# 05-TCXO_Crystal.net
KiCad netlist of a schematic drawn in Altium Designer
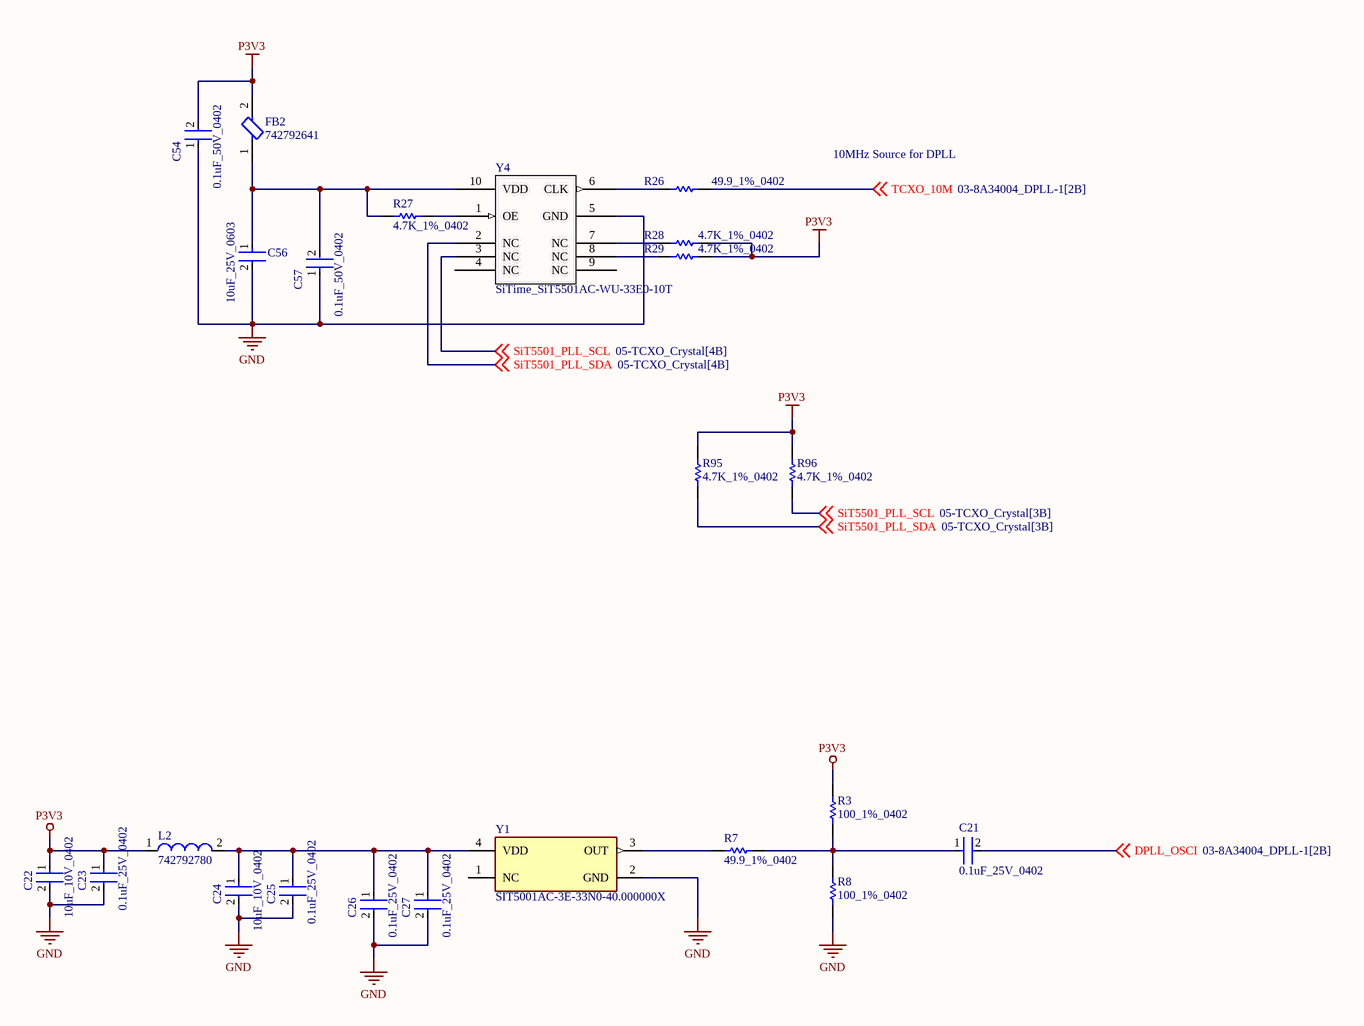
[diagram p0: 05-TCXO_Crystal.SchDoc]

(export (version "E")
  (design (tool "Eeschema 10.0.6"))
  (components
    (comp (ref "C21")
      (value "0.1uF_25V_0402")
      (footprint "FP-0402-L_1_0_1-W_0_5_0_1-IPC_C")
      (description "General Purpose Ceramic Capacitor, 0402, 100nF, 10%, X7R, 15%, 25V")
      (fields (field (name "VOLTAGE") "25V") (field (name "TOLERANCE") "10%"))
      (libsource (lib "Altium Content Vault") (part "b4654b650e69147ec39a6b967a45e02"))
    )
    (comp (ref "C22")
      (value "10uF_10V_0402")
      (footprint "FP-CL05A106MP5NUNC-MFG")
      (description "CAP CER 10UF 10V X5R 0402")
      (fields
        (field (name "OCTOPART") "https://octopart.com/cl05a106mp5nunc-samsung-22457395")
        (field (name "TOLERANCE") "20%")
      )
      (libsource (lib "Altium Content Vault") (part "b4654b650e69147ec39a6b967a45e02"))
    )
    (comp (ref "C23")
      (value "0.1uF_25V_0402")
      (footprint "FP-0402-L_1_0_1-W_0_5_0_1-IPC_C")
      (description "General Purpose Ceramic Capacitor, 0402, 100nF, 10%, X7R, 15%, 25V")
      (fields (field (name "VOLTAGE") "25V") (field (name "TOLERANCE") "10%"))
      (libsource (lib "Altium Content Vault") (part "b4654b650e69147ec39a6b967a45e02"))
    )
    (comp (ref "C24")
      (value "10uF_10V_0402")
      (footprint "FP-CL05A106MP5NUNC-MFG")
      (description "CAP CER 10UF 10V X5R 0402")
      (fields
        (field (name "OCTOPART") "https://octopart.com/cl05a106mp5nunc-samsung-22457395")
        (field (name "TOLERANCE") "20%")
      )
      (libsource (lib "Altium Content Vault") (part "b4654b650e69147ec39a6b967a45e02"))
    )
    (comp (ref "C25")
      (value "0.1uF_25V_0402")
      (footprint "FP-0402-L_1_0_1-W_0_5_0_1-IPC_C")
      (description "General Purpose Ceramic Capacitor, 0402, 100nF, 10%, X7R, 15%, 25V")
      (fields (field (name "VOLTAGE") "25V") (field (name "TOLERANCE") "10%"))
      (libsource (lib "Altium Content Vault") (part "b4654b650e69147ec39a6b967a45e02"))
    )
    (comp (ref "C26")
      (value "0.1uF_25V_0402")
      (footprint "FP-0402-L_1_0_1-W_0_5_0_1-IPC_C")
      (description "General Purpose Ceramic Capacitor, 0402, 100nF, 10%, X7R, 15%, 25V")
      (fields (field (name "VOLTAGE") "25V") (field (name "TOLERANCE") "10%"))
      (libsource (lib "Altium Content Vault") (part "b4654b650e69147ec39a6b967a45e02"))
    )
    (comp (ref "C27")
      (value "0.1uF_25V_0402")
      (footprint "FP-0402-L_1_0_1-W_0_5_0_1-IPC_C")
      (description "General Purpose Ceramic Capacitor, 0402, 100nF, 10%, X7R, 15%, 25V")
      (fields (field (name "VOLTAGE") "25V") (field (name "TOLERANCE") "10%"))
      (libsource (lib "Altium Content Vault") (part "b4654b650e69147ec39a6b967a45e02"))
    )
    (comp (ref "C54")
      (value "0.1uF_50V_0402")
      (footprint "FP-C1005-050-0_05-IPC_C")
      (description "Multilayer Ceramic Capacitors 100nF ±10% 50V X7R SMD 0402")
      (fields (field (name "VOLTAGE") "50V") (field (name "TOLERANCE") "10%"))
      (libsource (lib "Altium Content Vault") (part "b4654b650e69147ec39a6b967a45e02"))
    )
    (comp (ref "C56")
      (value "10uF_25V_0603")
      (footprint "FP-CL10-IPC_C")
      (description "Cap Ceramic 10uF 25V X5R ±20% Pad SMD 0603 +85°C T/R")
      (fields (field (name "TOLERANCE") "20%"))
      (libsource (lib "Altium Content Vault") (part "b4654b650e69147ec39a6b967a45e02"))
    )
    (comp (ref "C57")
      (value "0.1uF_50V_0402")
      (footprint "FP-C1005-050-0_05-IPC_C")
      (description "Multilayer Ceramic Capacitors 100nF ±10% 50V X7R SMD 0402")
      (fields (field (name "VOLTAGE") "50V") (field (name "TOLERANCE") "10%"))
      (libsource (lib "Altium Content Vault") (part "b4654b650e69147ec39a6b967a45e02"))
    )
    (comp (ref "FB2")
      (value "742792641")
      (footprint "FP-742792641-MFG")
      (description "FERRITE BEAD 300 OHM 0603 1LN")
      (fields (field (name "TOLERANCE") "25%"))
      (libsource (lib "Altium Content Vault") (part "5f30dd21d616792df468990f7003faa"))
    )
    (comp (ref "L2")
      (value "742792780")
      (footprint "SMD-0402")
      (description "SMD EMI Suppression Ferrite Bead WE-CBF, Z = 220 Ohm")
      (libsource (lib "Altium Content Vault") (part "PAS-IND-INDUCTOR-2"))
    )
    (comp (ref "R3")
      (value "100_1%_0402")
      (footprint "RESC1005X40X25ML05T10")
      (fields (field (name "PART NUMBER") "ERJ-U02F1000X") (field (name "MANUFACTURER") "Panasonic"))
      (libsource (lib "Altium Content Vault") (part "RES"))
    )
    (comp (ref "R7")
      (value "49.9_1%_0402")
      (footprint "RESC1005X40X25NL10T10")
      (fields (field (name "PART NUMBER") "RK73H1ETTP49R9F") (field (name "MANUFACTURER") "KOA Speer"))
      (libsource (lib "Altium Content Vault") (part "RES"))
    )
    (comp (ref "R8")
      (value "100_1%_0402")
      (footprint "RESC1005X40X25ML05T10")
      (fields (field (name "PART NUMBER") "ERJ-U02F1000X") (field (name "MANUFACTURER") "Panasonic"))
      (libsource (lib "Altium Content Vault") (part "RES"))
    )
    (comp (ref "R26")
      (value "49.9_1%_0402")
      (footprint "RESC1005X40X25NL10T10")
      (fields (field (name "PART NUMBER") "RK73H1ETTP49R9F") (field (name "MANUFACTURER") "KOA Speer"))
      (libsource (lib "Altium Content Vault") (part "RES"))
    )
    (comp (ref "R27")
      (value "4.7K_1%_0402")
      (footprint "RESC1005X40X25NL10T10")
      (fields (field (name "MANUFACTURER") "Bourns") (field (name "PART NUMBER") "CR0402-FX-4701GLF"))
      (libsource (lib "Altium Content Vault") (part "RES"))
    )
    (comp (ref "R28")
      (value "4.7K_1%_0402")
      (footprint "RESC1005X40X25NL10T10")
      (fields (field (name "MANUFACTURER") "Bourns") (field (name "PART NUMBER") "CR0402-FX-4701GLF"))
      (libsource (lib "Altium Content Vault") (part "RES"))
    )
    (comp (ref "R29")
      (value "4.7K_1%_0402")
      (footprint "RESC1005X40X25NL10T10")
      (fields (field (name "MANUFACTURER") "Bourns") (field (name "PART NUMBER") "CR0402-FX-4701GLF"))
      (libsource (lib "Altium Content Vault") (part "RES"))
    )
    (comp (ref "R95")
      (value "4.7K_1%_0402")
      (footprint "RESC1005X40X25NL10T10")
      (fields (field (name "MANUFACTURER") "Bourns") (field (name "PART NUMBER") "CR0402-FX-4701GLF"))
      (libsource (lib "Altium Content Vault") (part "RES"))
    )
    (comp (ref "R96")
      (value "4.7K_1%_0402")
      (footprint "RESC1005X40X25NL10T10")
      (fields (field (name "MANUFACTURER") "Bourns") (field (name "PART NUMBER") "CR0402-FX-4701GLF"))
      (libsource (lib "Altium Content Vault") (part "RES"))
    )
    (comp (ref "Y1")
      (value "SIT5001AC-3E-33N0-40.000000X")
      (footprint "FP-SiT5001-3-MFG")
      (description "MEMS OSC TCXO 40.0000MHZ LVCMOS")
      (libsource (lib "Altium Content Vault") (part "f2b4964c30f19ad016f2c5313c7e3e3"))
    )
    (comp (ref "Y4")
      (value "SiTime_SiT5501AC-WU-33E0-10T")
      (footprint "SITIME_SPL-086-CQFN-010-C07050_REV_DRAFT")
      (description "OSC, MEMS, STRATUM 3E, 10.000MHZ, 10PPB STAB, LVCMOS, 3.3V, O/P EN, 7.0X5.0X2.2MM, CQFN-10")
      (fields
        (field (name "MANUFACTURER PART NUMBER") "SiT5501AI-WU033JH-10.000000")
        (field (name "MANUFACTURER") "SiTime")
      )
      (libsource (lib "OCXO_DaughterCard") (part "CMP-OSC-00029-2"))
    )
  )
  (nets
    (net (code "1") (name "DPLL_OSCI") (class "Default")
      (node (ref "C21") (pin "2") (pinfunction "2_2") (pintype "passive"))
    )
    (net (code "2") (name "GND") (class "Default")
      (node (ref "C22") (pin "2") (pinfunction "2_2") (pintype "passive"))
      (node (ref "C23") (pin "2") (pinfunction "2_2") (pintype "passive"))
      (node (ref "C24") (pin "2") (pinfunction "2_2") (pintype "passive"))
      (node (ref "C25") (pin "2") (pinfunction "2_2") (pintype "passive"))
      (node (ref "C26") (pin "2") (pinfunction "2_2") (pintype "passive"))
      (node (ref "C27") (pin "2") (pinfunction "2_2") (pintype "passive"))
      (node (ref "C54") (pin "1") (pinfunction "1_1") (pintype "passive"))
      (node (ref "C56") (pin "2") (pinfunction "2_2") (pintype "passive"))
      (node (ref "C57") (pin "1") (pinfunction "1_1") (pintype "passive"))
      (node (ref "R8") (pin "1") (pinfunction "1_1") (pintype "passive"))
      (node (ref "Y1") (pin "2") (pinfunction "GND_2") (pintype "power_in"))
      (node (ref "Y4") (pin "5") (pinfunction "GND_5") (pintype "power_in"))
    )
    (net (code "3") (name "Net-(C21-Pad1)") (class "Default")
      (node (ref "C21") (pin "1") (pinfunction "1_1") (pintype "passive"))
      (node (ref "R3") (pin "1") (pinfunction "1_1") (pintype "passive"))
      (node (ref "R7") (pin "2") (pinfunction "2_2") (pintype "passive"))
      (node (ref "R8") (pin "2") (pinfunction "2_2") (pintype "passive"))
    )
    (net (code "4") (name "Net-(R28-Pad1)") (class "Default")
      (node (ref "R28") (pin "1") (pinfunction "1_1") (pintype "passive"))
      (node (ref "Y4") (pin "7") (pinfunction "NC_7") (pintype "passive"))
    )
    (net (code "5") (name "Net-(R29-Pad1)") (class "Default")
      (node (ref "R29") (pin "1") (pinfunction "1_1") (pintype "passive"))
      (node (ref "Y4") (pin "8") (pinfunction "NC_8") (pintype "passive"))
    )
    (net (code "6") (name "Net-(Y1-OUT)") (class "Default")
      (node (ref "R7") (pin "1") (pinfunction "1_1") (pintype "passive"))
      (node (ref "Y1") (pin "3") (pinfunction "OUT_3") (pintype "output"))
    )
    (net (code "7") (name "Net-(Y1-VDD)") (class "Default")
      (node (ref "C24") (pin "1") (pinfunction "1_1") (pintype "passive"))
      (node (ref "C25") (pin "1") (pinfunction "1_1") (pintype "passive"))
      (node (ref "C26") (pin "1") (pinfunction "1_1") (pintype "passive"))
      (node (ref "C27") (pin "1") (pinfunction "1_1") (pintype "passive"))
      (node (ref "L2") (pin "2") (pinfunction "2_2") (pintype "passive"))
      (node (ref "Y1") (pin "4") (pinfunction "VDD_4") (pintype "power_in"))
    )
    (net (code "8") (name "Net-(Y4-CLK)") (class "Default")
      (node (ref "R26") (pin "2") (pinfunction "2_2") (pintype "passive"))
      (node (ref "Y4") (pin "6") (pinfunction "CLK_6") (pintype "output"))
    )
    (net (code "9") (name "Net-(Y4-OE)") (class "Default")
      (node (ref "R27") (pin "2") (pinfunction "2_2") (pintype "passive"))
      (node (ref "Y4") (pin "1") (pinfunction "OE_1") (pintype "input"))
    )
    (net (code "10") (name "Net-(Y4-VDD)") (class "Default")
      (node (ref "C56") (pin "1") (pinfunction "1_1") (pintype "passive"))
      (node (ref "C57") (pin "2") (pinfunction "2_2") (pintype "passive"))
      (node (ref "FB2") (pin "1") (pinfunction "1_1") (pintype "passive"))
      (node (ref "R27") (pin "1") (pinfunction "1_1") (pintype "passive"))
      (node (ref "Y4") (pin "10") (pinfunction "VDD_10") (pintype "power_in"))
    )
    (net (code "11") (name "P3V3") (class "Default")
      (node (ref "C22") (pin "1") (pinfunction "1_1") (pintype "passive"))
      (node (ref "C23") (pin "1") (pinfunction "1_1") (pintype "passive"))
      (node (ref "C54") (pin "2") (pinfunction "2_2") (pintype "passive"))
      (node (ref "FB2") (pin "2") (pinfunction "2_2") (pintype "passive"))
      (node (ref "L2") (pin "1") (pinfunction "1_1") (pintype "passive"))
      (node (ref "R28") (pin "2") (pinfunction "2_2") (pintype "passive"))
      (node (ref "R29") (pin "2") (pinfunction "2_2") (pintype "passive"))
      (node (ref "R3") (pin "2") (pinfunction "2_2") (pintype "passive"))
      (node (ref "R95") (pin "2") (pinfunction "2_2") (pintype "passive"))
      (node (ref "R96") (pin "2") (pinfunction "2_2") (pintype "passive"))
    )
    (net (code "12") (name "SiT5501_PLL_SCL") (class "Default")
      (node (ref "R96") (pin "1") (pinfunction "1_1") (pintype "passive"))
      (node (ref "Y4") (pin "3") (pinfunction "NC_3") (pintype "passive"))
    )
    (net (code "13") (name "SiT5501_PLL_SDA") (class "Default")
      (node (ref "R95") (pin "1") (pinfunction "1_1") (pintype "passive"))
      (node (ref "Y4") (pin "2") (pinfunction "NC_2") (pintype "passive"))
    )
    (net (code "14") (name "TCXO_10M") (class "Default")
      (node (ref "R26") (pin "1") (pinfunction "1_1") (pintype "passive"))
    )
    (net (code "15") (name "unconnected-(Y1-NC-Pad1)") (class "Default")
      (node (ref "Y1") (pin "1") (pinfunction "NC_1") (pintype "passive"))
    )
    (net (code "16") (name "unconnected-(Y4-NC-Pad4)") (class "Default")
      (node (ref "Y4") (pin "4") (pinfunction "NC_4") (pintype "passive"))
    )
    (net (code "17") (name "unconnected-(Y4-NC-Pad9)") (class "Default")
      (node (ref "Y4") (pin "9") (pinfunction "NC_9") (pintype "passive"))
    )
  )
)
